# CarrierPeripherals.net
KiCad netlist of a schematic drawn in Altium Designer
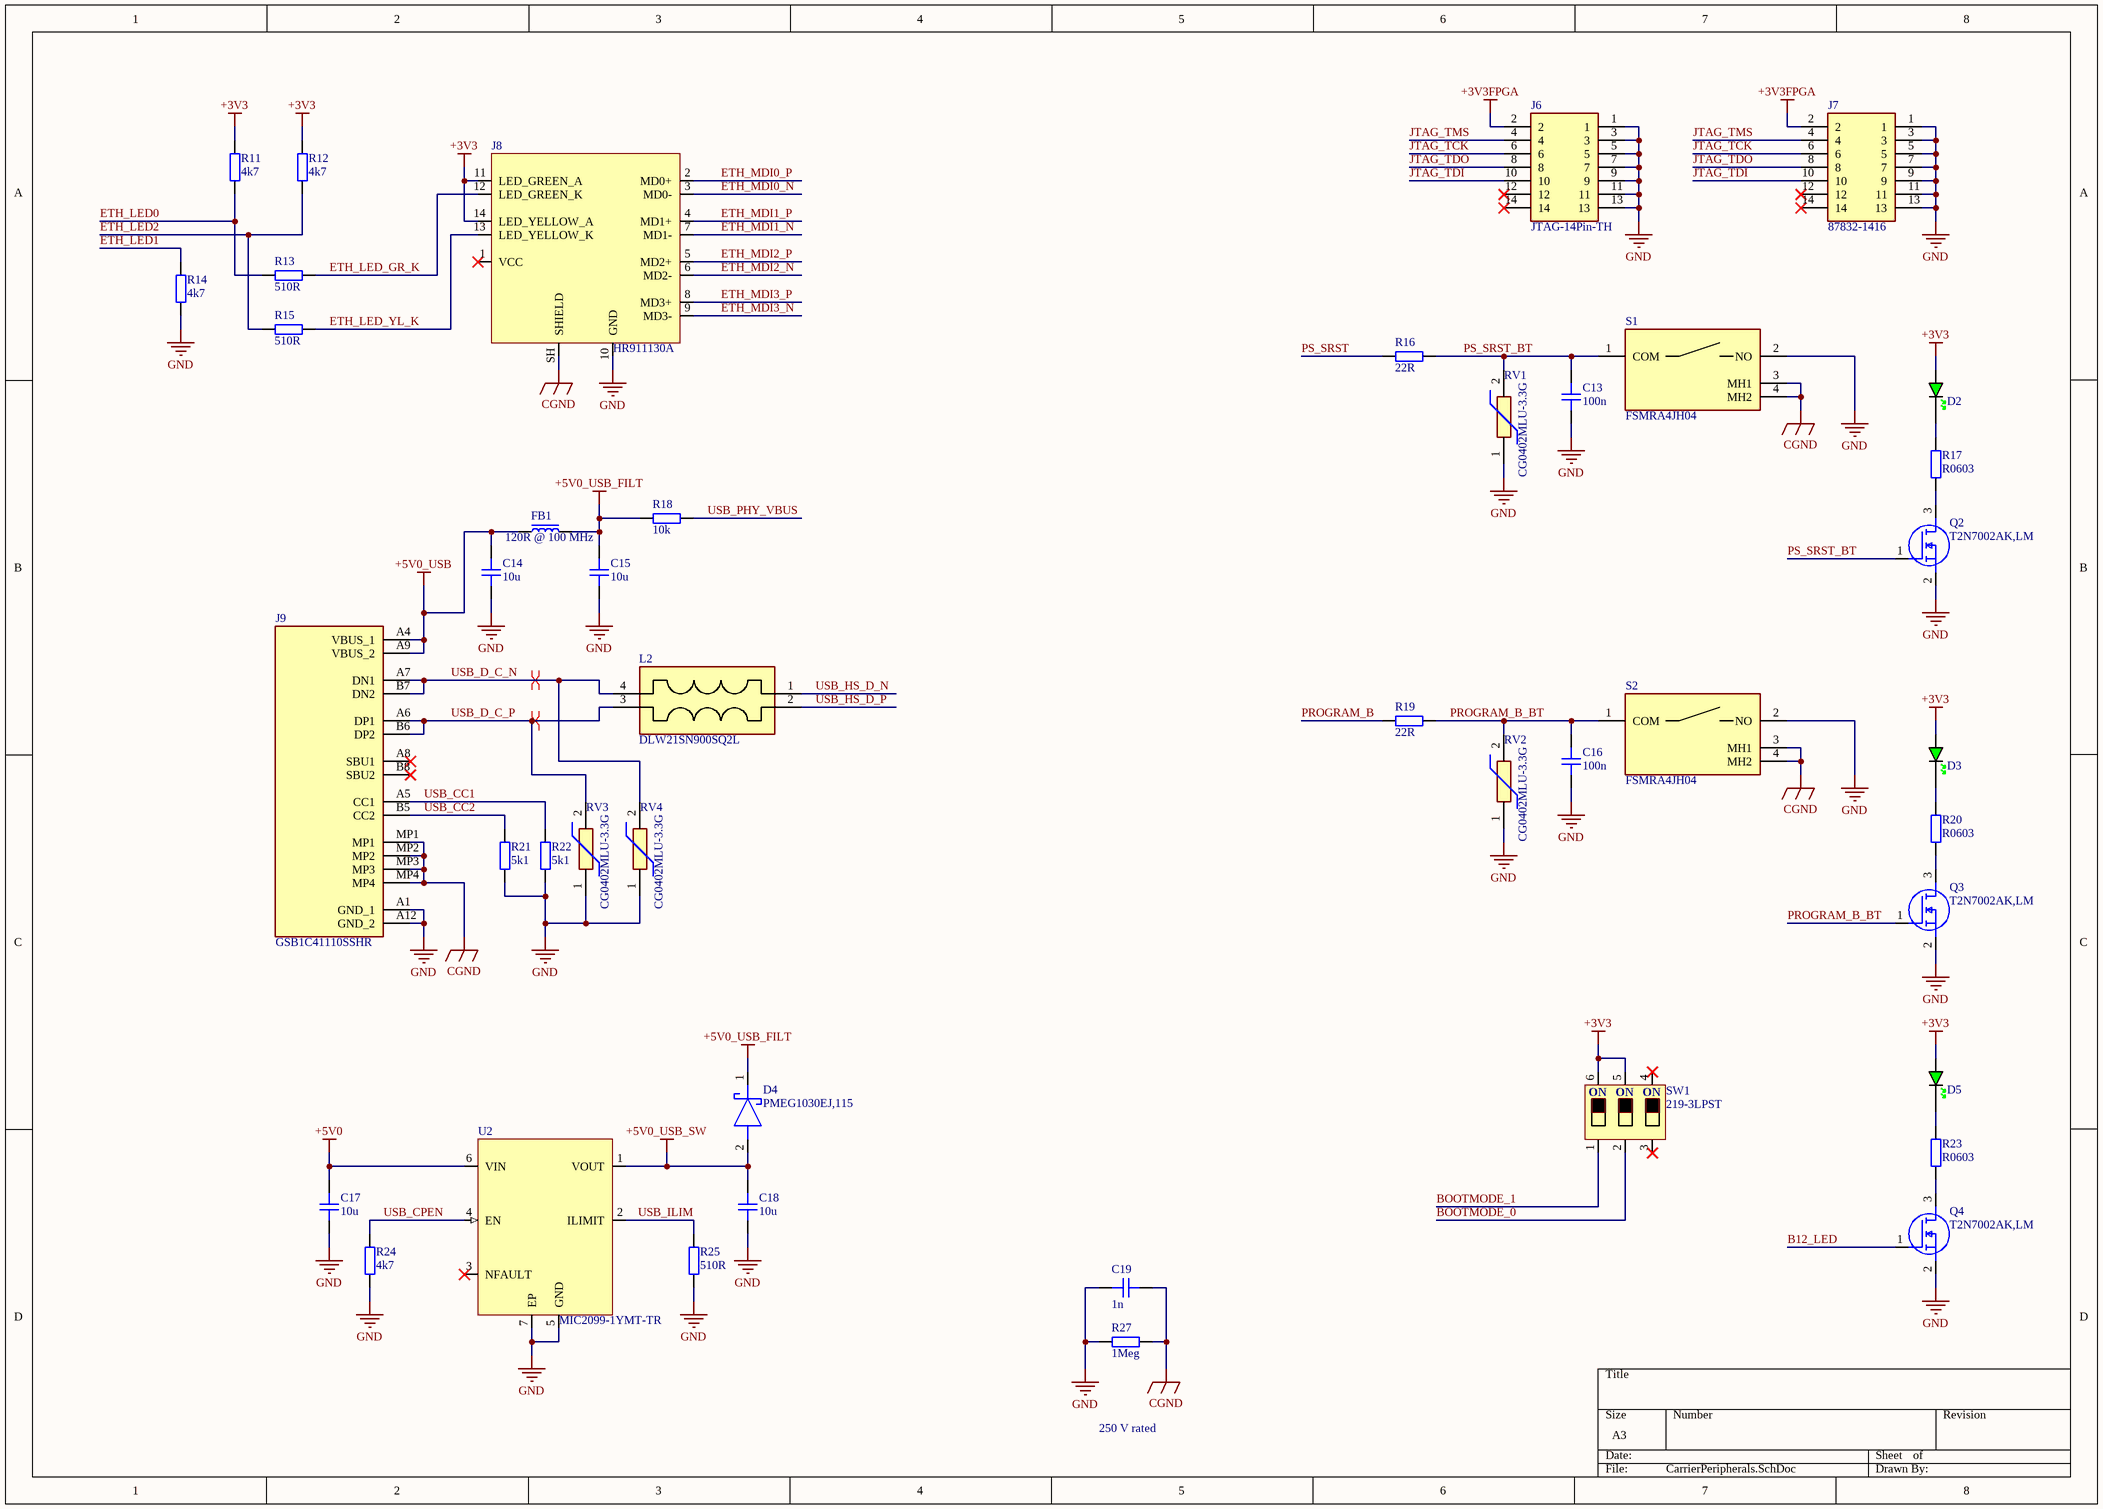
[diagram p0: CarrierPeripherals.SchDoc]

(export (version "E")
  (design (tool "Eeschema 10.0.6"))
  (components
    (comp (ref "C13")
      (value "100n")
      (footprint "CAP_0402")
      (description "Capacitor SMD 0402")
      (libsource (lib "Schematic-Lib-PhilsLab") (part "CAP_0402"))
    )
    (comp (ref "C14")
      (value "10u")
      (footprint "CAP_0603")
      (description "Capacitor SMD 0603")
      (libsource (lib "Schematic-Lib-PhilsLab") (part "CAP_0603"))
    )
    (comp (ref "C15")
      (value "10u")
      (footprint "CAP_0603")
      (description "Capacitor SMD 0603")
      (libsource (lib "Schematic-Lib-PhilsLab") (part "CAP_0603"))
    )
    (comp (ref "C16")
      (value "100n")
      (footprint "CAP_0402")
      (description "Capacitor SMD 0402")
      (libsource (lib "Schematic-Lib-PhilsLab") (part "CAP_0402"))
    )
    (comp (ref "C17")
      (value "10u")
      (footprint "CAP_0603")
      (description "Capacitor SMD 0603")
      (libsource (lib "Schematic-Lib-PhilsLab") (part "CAP_0603"))
    )
    (comp (ref "C18")
      (value "10u")
      (footprint "CAP_0603")
      (description "Capacitor SMD 0603")
      (libsource (lib "Schematic-Lib-PhilsLab") (part "CAP_0603"))
    )
    (comp (ref "C19")
      (value "1n")
      (footprint "CAP_1206")
      (description "Capacitor SMD 1206")
      (libsource (lib "Schematic-Lib-PhilsLab") (part "CAP_1206"))
    )
    (comp (ref "D2")
      (value "GREEN")
      (footprint "LED_0603_GREEN")
      (description "LED 0603 GREEN SMD")
      (libsource (lib "Schematic-Lib-PhilsLab") (part "LED_0603_GREEN"))
    )
    (comp (ref "D3")
      (value "GREEN")
      (footprint "LED_0603_GREEN")
      (description "LED 0603 GREEN SMD")
      (libsource (lib "Schematic-Lib-PhilsLab") (part "LED_0603_GREEN"))
    )
    (comp (ref "D4")
      (value "PMEG1030EJ,115")
      (footprint "CarrierBoardPCBLib:PMEG1030EJ115")
      (description "Schottky Diode")
      (fields (field (name "MOUSER PART NUMBER") "771-PMEG1030EJ-T/R"))
      (libsource (lib "CarrierBoardSCHLib") (part "PMEG1030EJ,115"))
    )
    (comp (ref "D5")
      (value "GREEN")
      (footprint "LED_0603_GREEN")
      (description "LED 0603 GREEN SMD")
      (libsource (lib "Schematic-Lib-PhilsLab") (part "LED_0603_GREEN"))
    )
    (comp (ref "FB1")
      (value "120R @ 100 MHz")
      (footprint "FB_0603")
      (description "Ferrite Bead SMD 0603")
      (libsource (lib "Schematic-Lib-PhilsLab") (part "FB_0603"))
    )
    (comp (ref "J6")
      (value "JTAG-14Pin-TH")
      (footprint "XC7Z030PCBLib:14Pin-TH")
      (description "Connector")
      (fields
        (field (name "MANUFACTURER_PART_NUMBER") "87832-1416")
        (field (name "MOUSER PART NUMBER") "538-87832-1416")
      )
      (libsource (lib "XC7Z030SCHLib") (part "JTAG-14Pin-TH"))
    )
    (comp (ref "J7")
      (value "87832-1416")
      (footprint "XC7Z030PCBLib:878321416")
      (description "Connector")
      (fields (field (name "MOUSER PART NUMBER") "538-87832-1416"))
      (libsource (lib "XC7Z030SCHLib") (part "87832-1416"))
    )
    (comp (ref "J8")
      (value "HR911130A")
      (footprint "HR911130A")
      (description "100/1000Base-T Magnetics Single-Port RJ45 Connector with Integrated Magnetics and LEDs")
      (fields (field (name "MANUFACTURER") "Hanrun"))
      (libsource (lib "Schematic-Lib-PhilsLab") (part "HR911130A"))
    )
    (comp (ref "J9")
      (value "GSB1C41110SSHR")
      (footprint "XC7Z030PCBLib:GSB1C41110SSHR")
      (description "Connector")
      (libsource (lib "XC7Z030SCHLib") (part "GSB1C41110SSHR"))
    )
    (comp (ref "L2")
      (value "DLW21SN900SQ2L")
      (footprint "CarrierBoardPCBLib:DLW21SN121HQ2L")
      (description "Inductor")
      (fields (field (name "MOUSER PART NUMBER") "81-DLW21SN900SQ2L"))
      (libsource (lib "CarrierBoardSCHLib") (part "DLW21SN900SQ2L"))
    )
    (comp (ref "Q2")
      (value "T2N7002AK,LM")
      (footprint "Footprint-Lib-PhilsLab:TBAT54CLM")
      (description "MOSFET (N-Channel)")
      (fields (field (name "MOUSER PART NUMBER") "757-T2N7002AKLM"))
      (libsource (lib "Schematic-Lib-PhilsLab") (part "T2N7002AK,LM"))
    )
    (comp (ref "Q3")
      (value "T2N7002AK,LM")
      (footprint "Footprint-Lib-PhilsLab:TBAT54CLM")
      (description "MOSFET (N-Channel)")
      (fields (field (name "MOUSER PART NUMBER") "757-T2N7002AKLM"))
      (libsource (lib "Schematic-Lib-PhilsLab") (part "T2N7002AK,LM"))
    )
    (comp (ref "Q4")
      (value "T2N7002AK,LM")
      (footprint "Footprint-Lib-PhilsLab:TBAT54CLM")
      (description "MOSFET (N-Channel)")
      (fields (field (name "MOUSER PART NUMBER") "757-T2N7002AKLM"))
      (libsource (lib "Schematic-Lib-PhilsLab") (part "T2N7002AK,LM"))
    )
    (comp (ref "R11")
      (value "4k7")
      (footprint "RES_0402")
      (description "Resistor SMD 0402")
      (libsource (lib "Schematic-Lib-PhilsLab") (part "RES_0402"))
    )
    (comp (ref "R12")
      (value "4k7")
      (footprint "RES_0402")
      (description "Resistor SMD 0402")
      (libsource (lib "Schematic-Lib-PhilsLab") (part "RES_0402"))
    )
    (comp (ref "R13")
      (value "510R")
      (footprint "RES_0603")
      (description "Resistor SMD 0603")
      (libsource (lib "Schematic-Lib-PhilsLab") (part "RES_0603"))
    )
    (comp (ref "R14")
      (value "4k7")
      (footprint "RES_0402")
      (description "Resistor SMD 0402")
      (libsource (lib "Schematic-Lib-PhilsLab") (part "RES_0402"))
    )
    (comp (ref "R15")
      (value "510R")
      (footprint "RES_0603")
      (description "Resistor SMD 0603")
      (libsource (lib "Schematic-Lib-PhilsLab") (part "RES_0603"))
    )
    (comp (ref "R16")
      (value "22R")
      (footprint "RES_0402")
      (description "Resistor SMD 0402")
      (libsource (lib "Schematic-Lib-PhilsLab") (part "RES_0402"))
    )
    (comp (ref "R17")
      (value "R0603")
      (footprint "RES_0603")
      (description "Resistor SMD 0603")
      (libsource (lib "Schematic-Lib-PhilsLab") (part "RES_0603"))
    )
    (comp (ref "R18")
      (value "10k")
      (footprint "RES_0402")
      (description "Resistor SMD 0402")
      (libsource (lib "Schematic-Lib-PhilsLab") (part "RES_0402"))
    )
    (comp (ref "R19")
      (value "22R")
      (footprint "RES_0402")
      (description "Resistor SMD 0402")
      (libsource (lib "Schematic-Lib-PhilsLab") (part "RES_0402"))
    )
    (comp (ref "R20")
      (value "R0603")
      (footprint "RES_0603")
      (description "Resistor SMD 0603")
      (libsource (lib "Schematic-Lib-PhilsLab") (part "RES_0603"))
    )
    (comp (ref "R21")
      (value "5k1")
      (footprint "RES_0402")
      (description "Resistor SMD 0402")
      (libsource (lib "Schematic-Lib-PhilsLab") (part "RES_0402"))
    )
    (comp (ref "R22")
      (value "5k1")
      (footprint "RES_0402")
      (description "Resistor SMD 0402")
      (libsource (lib "Schematic-Lib-PhilsLab") (part "RES_0402"))
    )
    (comp (ref "R23")
      (value "R0603")
      (footprint "RES_0603")
      (description "Resistor SMD 0603")
      (libsource (lib "Schematic-Lib-PhilsLab") (part "RES_0603"))
    )
    (comp (ref "R24")
      (value "4k7")
      (footprint "RES_0402")
      (description "Resistor SMD 0402")
      (libsource (lib "Schematic-Lib-PhilsLab") (part "RES_0402"))
    )
    (comp (ref "R25")
      (value "510R")
      (footprint "RES_0603")
      (description "Resistor SMD 0603")
      (libsource (lib "Schematic-Lib-PhilsLab") (part "RES_0603"))
    )
    (comp (ref "R27")
      (value "1Meg")
      (footprint "RES_1206")
      (description "Resistor SMD 1206")
      (libsource (lib "Schematic-Lib-PhilsLab") (part "RES_1206"))
    )
    (comp (ref "RV1")
      (value "CG0402MLU-3.3G")
      (footprint "CarrierBoardPCBLib:VARC1005X41N")
      (description "ESD Diode")
      (fields (field (name "MOUSER PART NUMBER") "652-CG0402MLU-3.3G"))
      (libsource (lib "CarrierBoardSCHLib") (part "CG0402MLU-3.3G"))
    )
    (comp (ref "RV2")
      (value "CG0402MLU-3.3G")
      (footprint "CarrierBoardPCBLib:VARC1005X41N")
      (description "ESD Diode")
      (fields (field (name "MOUSER PART NUMBER") "652-CG0402MLU-3.3G"))
      (libsource (lib "CarrierBoardSCHLib") (part "CG0402MLU-3.3G"))
    )
    (comp (ref "RV3")
      (value "CG0402MLU-3.3G")
      (footprint "CarrierBoardPCBLib:VARC1005X41N")
      (description "ESD Diode")
      (fields (field (name "MOUSER PART NUMBER") "652-CG0402MLU-3.3G"))
      (libsource (lib "CarrierBoardSCHLib") (part "CG0402MLU-3.3G"))
    )
    (comp (ref "RV4")
      (value "CG0402MLU-3.3G")
      (footprint "CarrierBoardPCBLib:VARC1005X41N")
      (description "ESD Diode")
      (fields (field (name "MOUSER PART NUMBER") "652-CG0402MLU-3.3G"))
      (libsource (lib "CarrierBoardSCHLib") (part "CG0402MLU-3.3G"))
    )
    (comp (ref "S1")
      (value "FSMRA4JH04")
      (footprint "CarrierBoardPCBLib:FSMRA4JH04")
      (description "Switch")
      (fields (field (name "MOUSER PART NUMBER") "506-FSMRA4JH04"))
      (libsource (lib "CarrierBoardSCHLib") (part "FSMRA4JH04"))
    )
    (comp (ref "S2")
      (value "FSMRA4JH04")
      (footprint "CarrierBoardPCBLib:FSMRA4JH04")
      (description "Switch")
      (fields (field (name "MOUSER PART NUMBER") "506-FSMRA4JH04"))
      (libsource (lib "CarrierBoardSCHLib") (part "FSMRA4JH04"))
    )
    (comp (ref "SW1")
      (value "219-3LPST")
      (footprint "219-3LPST")
      (description "DIP Switches SPST 3x")
      (fields (field (name "MANUFACTURER") "CTS"))
      (libsource (lib "Schematic-Lib-PhilsLab") (part "219-3LPST"))
    )
    (comp (ref "U2")
      (value "MIC2099-1YMT-TR")
      (footprint "TMLF-6-1_6X1_6")
      (description "Power Distribution Switch Resistor programmable current limit\r\n– 0.1A to 1.1A 2.5V-5.5V")
      (fields (field (name "MANUFACTURER") "Microchip"))
      (libsource (lib "Schematic-Lib-PhilsLab") (part "MIC2099-1YMT-TR"))
    )
  )
  (nets
    (net (code "1") (name "+3V3") (class "Default")
      (node (ref "D2") (pin "A") (pinfunction "A_A") (pintype "passive"))
      (node (ref "D3") (pin "A") (pinfunction "A_A") (pintype "passive"))
      (node (ref "D5") (pin "A") (pinfunction "A_A") (pintype "passive"))
      (node (ref "J8") (pin "11") (pinfunction "LED_GREEN_A_11") (pintype "passive"))
      (node (ref "J8") (pin "14") (pinfunction "LED_YELLOW_A_14") (pintype "passive"))
      (node (ref "R11") (pin "2") (pinfunction "2_2") (pintype "passive"))
      (node (ref "R12") (pin "2") (pinfunction "2_2") (pintype "passive"))
      (node (ref "SW1") (pin "5") (pinfunction "5_5") (pintype "passive"))
      (node (ref "SW1") (pin "6") (pinfunction "6_6") (pintype "passive"))
    )
    (net (code "2") (name "+3V3FPGA") (class "Default")
      (node (ref "J6") (pin "2") (pinfunction "2_2") (pintype "passive"))
      (node (ref "J7") (pin "2") (pinfunction "2_2") (pintype "passive"))
    )
    (net (code "3") (name "+5V0") (class "Default")
      (node (ref "C17") (pin "2") (pinfunction "2_2") (pintype "passive"))
      (node (ref "U2") (pin "6") (pinfunction "VIN_6") (pintype "power_in"))
    )
    (net (code "4") (name "+5V0_USB") (class "Default")
      (node (ref "C14") (pin "2") (pinfunction "2_2") (pintype "passive"))
      (node (ref "FB1") (pin "1") (pinfunction "1_1") (pintype "passive"))
      (node (ref "J9") (pin "A4") (pinfunction "VBUS_1_A4") (pintype "passive"))
      (node (ref "J9") (pin "A9") (pinfunction "VBUS_2_A9") (pintype "passive"))
    )
    (net (code "5") (name "+5V0_USB_FILT") (class "Default")
      (node (ref "C15") (pin "2") (pinfunction "2_2") (pintype "passive"))
      (node (ref "D4") (pin "1") (pinfunction "K_1") (pintype "passive"))
      (node (ref "FB1") (pin "2") (pinfunction "2_2") (pintype "passive"))
      (node (ref "R18") (pin "1") (pinfunction "1_1") (pintype "passive"))
    )
    (net (code "6") (name "+5V0_USB_SW") (class "Default")
      (node (ref "C18") (pin "2") (pinfunction "2_2") (pintype "passive"))
      (node (ref "D4") (pin "2") (pinfunction "A_2") (pintype "passive"))
      (node (ref "U2") (pin "1") (pinfunction "VOUT_1") (pintype "power_in"))
    )
    (net (code "7") (name "/B12_LED") (class "Default")
      (node (ref "Q4") (pin "1") (pinfunction "G_1") (pintype "passive"))
    )
    (net (code "8") (name "/BOOTMODE_0") (class "Default")
      (node (ref "SW1") (pin "2") (pinfunction "2_2") (pintype "passive"))
    )
    (net (code "9") (name "/BOOTMODE_1") (class "Default")
      (node (ref "SW1") (pin "1") (pinfunction "1_1") (pintype "passive"))
    )
    (net (code "10") (name "/ETH_LED0") (class "Default")
      (node (ref "R11") (pin "1") (pinfunction "1_1") (pintype "passive"))
      (node (ref "R13") (pin "1") (pinfunction "1_1") (pintype "passive"))
    )
    (net (code "11") (name "/ETH_LED1") (class "Default")
      (node (ref "R14") (pin "2") (pinfunction "2_2") (pintype "passive"))
    )
    (net (code "12") (name "/ETH_LED2") (class "Default")
      (node (ref "R12") (pin "1") (pinfunction "1_1") (pintype "passive"))
      (node (ref "R15") (pin "2") (pinfunction "2_2") (pintype "passive"))
    )
    (net (code "13") (name "/ETH_LED_GR_K") (class "Default")
      (node (ref "J8") (pin "12") (pinfunction "LED_GREEN_K_12") (pintype "passive"))
      (node (ref "R13") (pin "2") (pinfunction "2_2") (pintype "passive"))
    )
    (net (code "14") (name "/ETH_LED_YL_K") (class "Default")
      (node (ref "J8") (pin "13") (pinfunction "LED_YELLOW_K_13") (pintype "passive"))
      (node (ref "R15") (pin "1") (pinfunction "1_1") (pintype "passive"))
    )
    (net (code "15") (name "/ETH_MDI0_N") (class "Default")
      (node (ref "J8") (pin "3") (pinfunction "MD0-_3") (pintype "passive"))
    )
    (net (code "16") (name "/ETH_MDI0_P") (class "Default")
      (node (ref "J8") (pin "2") (pinfunction "MD0+_2") (pintype "passive"))
    )
    (net (code "17") (name "/ETH_MDI1_N") (class "Default")
      (node (ref "J8") (pin "7") (pinfunction "MD1-_7") (pintype "passive"))
    )
    (net (code "18") (name "/ETH_MDI1_P") (class "Default")
      (node (ref "J8") (pin "4") (pinfunction "MD1+_4") (pintype "passive"))
    )
    (net (code "19") (name "/ETH_MDI2_N") (class "Default")
      (node (ref "J8") (pin "6") (pinfunction "MD2-_6") (pintype "passive"))
    )
    (net (code "20") (name "/ETH_MDI2_P") (class "Default")
      (node (ref "J8") (pin "5") (pinfunction "MD2+_5") (pintype "passive"))
    )
    (net (code "21") (name "/ETH_MDI3_N") (class "Default")
      (node (ref "J8") (pin "9") (pinfunction "MD3-_9") (pintype "passive"))
    )
    (net (code "22") (name "/ETH_MDI3_P") (class "Default")
      (node (ref "J8") (pin "8") (pinfunction "MD3+_8") (pintype "passive"))
    )
    (net (code "23") (name "/JTAG_TCK") (class "Default")
      (node (ref "J6") (pin "6") (pinfunction "6_6") (pintype "passive"))
      (node (ref "J7") (pin "6") (pinfunction "6_6") (pintype "passive"))
    )
    (net (code "24") (name "/JTAG_TDI") (class "Default")
      (node (ref "J6") (pin "10") (pinfunction "10_10") (pintype "passive"))
      (node (ref "J7") (pin "10") (pinfunction "10_10") (pintype "passive"))
    )
    (net (code "25") (name "/JTAG_TDO") (class "Default")
      (node (ref "J6") (pin "8") (pinfunction "8_8") (pintype "passive"))
      (node (ref "J7") (pin "8") (pinfunction "8_8") (pintype "passive"))
    )
    (net (code "26") (name "/JTAG_TMS") (class "Default")
      (node (ref "J6") (pin "4") (pinfunction "4_4") (pintype "passive"))
      (node (ref "J7") (pin "4") (pinfunction "4_4") (pintype "passive"))
    )
    (net (code "27") (name "/PROGRAM_B") (class "Default")
      (node (ref "R19") (pin "2") (pinfunction "2_2") (pintype "passive"))
    )
    (net (code "28") (name "/PROGRAM_B_BT") (class "Default")
      (node (ref "C16") (pin "2") (pinfunction "2_2") (pintype "passive"))
      (node (ref "Q3") (pin "1") (pinfunction "G_1") (pintype "passive"))
      (node (ref "R19") (pin "1") (pinfunction "1_1") (pintype "passive"))
      (node (ref "RV2") (pin "2") (pinfunction "2_2") (pintype "passive"))
      (node (ref "S2") (pin "1") (pinfunction "COM_1") (pintype "passive"))
    )
    (net (code "29") (name "/PS_SRST") (class "Default")
      (node (ref "R16") (pin "2") (pinfunction "2_2") (pintype "passive"))
    )
    (net (code "30") (name "/PS_SRST_BT") (class "Default")
      (node (ref "C13") (pin "2") (pinfunction "2_2") (pintype "passive"))
      (node (ref "Q2") (pin "1") (pinfunction "G_1") (pintype "passive"))
      (node (ref "R16") (pin "1") (pinfunction "1_1") (pintype "passive"))
      (node (ref "RV1") (pin "2") (pinfunction "2_2") (pintype "passive"))
      (node (ref "S1") (pin "1") (pinfunction "COM_1") (pintype "passive"))
    )
    (net (code "31") (name "/USB_CC1") (class "Default")
      (node (ref "J9") (pin "A5") (pinfunction "CC1_A5") (pintype "passive"))
      (node (ref "R22") (pin "2") (pinfunction "2_2") (pintype "passive"))
    )
    (net (code "32") (name "/USB_CC2") (class "Default")
      (node (ref "J9") (pin "B5") (pinfunction "CC2_B5") (pintype "passive"))
      (node (ref "R21") (pin "2") (pinfunction "2_2") (pintype "passive"))
    )
    (net (code "33") (name "/USB_CPEN") (class "Default")
      (node (ref "R24") (pin "2") (pinfunction "2_2") (pintype "passive"))
      (node (ref "U2") (pin "4") (pinfunction "EN_4") (pintype "input"))
    )
    (net (code "34") (name "/USB_D_C_N") (class "Default")
      (node (ref "J9") (pin "A7") (pinfunction "DN1_A7") (pintype "passive"))
      (node (ref "J9") (pin "B7") (pinfunction "DN2_B7") (pintype "passive"))
      (node (ref "L2") (pin "4") (pintype "passive"))
      (node (ref "RV4") (pin "2") (pinfunction "2_2") (pintype "passive"))
    )
    (net (code "35") (name "/USB_D_C_P") (class "Default")
      (node (ref "J9") (pin "A6") (pinfunction "DP1_A6") (pintype "passive"))
      (node (ref "J9") (pin "B6") (pinfunction "DP2_B6") (pintype "passive"))
      (node (ref "L2") (pin "3") (pintype "passive"))
      (node (ref "RV3") (pin "2") (pinfunction "2_2") (pintype "passive"))
    )
    (net (code "36") (name "/USB_HS_D_N") (class "Default") (node (ref "L2") (pin "1") (pintype "passive")))
    (net (code "37") (name "/USB_HS_D_P") (class "Default") (node (ref "L2") (pin "2") (pintype "passive")))
    (net (code "38") (name "/USB_ILIM") (class "Default")
      (node (ref "R25") (pin "2") (pinfunction "2_2") (pintype "passive"))
      (node (ref "U2") (pin "2") (pinfunction "ILIMIT_2") (pintype "passive"))
    )
    (net (code "39") (name "/USB_PHY_VBUS") (class "Default")
      (node (ref "R18") (pin "2") (pinfunction "2_2") (pintype "passive"))
    )
    (net (code "40") (name "CGND") (class "Default")
      (node (ref "C19") (pin "2") (pinfunction "2_2") (pintype "passive"))
      (node (ref "J8") (pin "SH") (pinfunction "SHIELD_SH") (pintype "passive"))
      (node (ref "J9") (pin "MP1") (pinfunction "MP1_MP1") (pintype "passive"))
      (node (ref "J9") (pin "MP2") (pinfunction "MP2_MP2") (pintype "passive"))
      (node (ref "J9") (pin "MP3") (pinfunction "MP3_MP3") (pintype "passive"))
      (node (ref "J9") (pin "MP4") (pinfunction "MP4_MP4") (pintype "passive"))
      (node (ref "R27") (pin "2") (pinfunction "2_2") (pintype "passive"))
      (node (ref "S1") (pin "3") (pinfunction "MH1_3") (pintype "passive"))
      (node (ref "S1") (pin "4") (pinfunction "MH2_4") (pintype "passive"))
      (node (ref "S2") (pin "3") (pinfunction "MH1_3") (pintype "passive"))
      (node (ref "S2") (pin "4") (pinfunction "MH2_4") (pintype "passive"))
    )
    (net (code "41") (name "GND") (class "Default")
      (node (ref "C13") (pin "1") (pinfunction "1_1") (pintype "passive"))
      (node (ref "C14") (pin "1") (pinfunction "1_1") (pintype "passive"))
      (node (ref "C15") (pin "1") (pinfunction "1_1") (pintype "passive"))
      (node (ref "C16") (pin "1") (pinfunction "1_1") (pintype "passive"))
      (node (ref "C17") (pin "1") (pinfunction "1_1") (pintype "passive"))
      (node (ref "C18") (pin "1") (pinfunction "1_1") (pintype "passive"))
      (node (ref "C19") (pin "1") (pinfunction "1_1") (pintype "passive"))
      (node (ref "J6") (pin "1") (pinfunction "1_1") (pintype "passive"))
      (node (ref "J6") (pin "11") (pinfunction "11_11") (pintype "passive"))
      (node (ref "J6") (pin "13") (pinfunction "13_13") (pintype "passive"))
      (node (ref "J6") (pin "3") (pinfunction "3_3") (pintype "passive"))
      (node (ref "J6") (pin "5") (pinfunction "5_5") (pintype "passive"))
      (node (ref "J6") (pin "7") (pinfunction "7_7") (pintype "passive"))
      (node (ref "J6") (pin "9") (pinfunction "9_9") (pintype "passive"))
      (node (ref "J7") (pin "1") (pinfunction "1_1") (pintype "passive"))
      (node (ref "J7") (pin "11") (pinfunction "11_11") (pintype "passive"))
      (node (ref "J7") (pin "13") (pinfunction "13_13") (pintype "passive"))
      (node (ref "J7") (pin "3") (pinfunction "3_3") (pintype "passive"))
      (node (ref "J7") (pin "5") (pinfunction "5_5") (pintype "passive"))
      (node (ref "J7") (pin "7") (pinfunction "7_7") (pintype "passive"))
      (node (ref "J7") (pin "9") (pinfunction "9_9") (pintype "passive"))
      (node (ref "J8") (pin "10") (pinfunction "GND_10") (pintype "passive"))
      (node (ref "J9") (pin "A1") (pinfunction "GND_1_A1") (pintype "passive"))
      (node (ref "J9") (pin "A12") (pinfunction "GND_2_A12") (pintype "passive"))
      (node (ref "Q2") (pin "2") (pinfunction "S_2") (pintype "passive"))
      (node (ref "Q3") (pin "2") (pinfunction "S_2") (pintype "passive"))
      (node (ref "Q4") (pin "2") (pinfunction "S_2") (pintype "passive"))
      (node (ref "R14") (pin "1") (pinfunction "1_1") (pintype "passive"))
      (node (ref "R21") (pin "1") (pinfunction "1_1") (pintype "passive"))
      (node (ref "R22") (pin "1") (pinfunction "1_1") (pintype "passive"))
      (node (ref "R24") (pin "1") (pinfunction "1_1") (pintype "passive"))
      (node (ref "R25") (pin "1") (pinfunction "1_1") (pintype "passive"))
      (node (ref "R27") (pin "1") (pinfunction "1_1") (pintype "passive"))
      (node (ref "RV1") (pin "1") (pinfunction "1_1") (pintype "passive"))
      (node (ref "RV2") (pin "1") (pinfunction "1_1") (pintype "passive"))
      (node (ref "RV3") (pin "1") (pinfunction "1_1") (pintype "passive"))
      (node (ref "RV4") (pin "1") (pinfunction "1_1") (pintype "passive"))
      (node (ref "S1") (pin "2") (pinfunction "NO_2") (pintype "passive"))
      (node (ref "S2") (pin "2") (pinfunction "NO_2") (pintype "passive"))
      (node (ref "U2") (pin "5") (pinfunction "GND_5") (pintype "power_in"))
      (node (ref "U2") (pin "7") (pinfunction "EP_7") (pintype "power_in"))
    )
    (net (code "42") (name "Net-(D2-PadK)") (class "Default")
      (node (ref "D2") (pin "K") (pinfunction "K_K") (pintype "passive"))
      (node (ref "R17") (pin "2") (pinfunction "2_2") (pintype "passive"))
    )
    (net (code "43") (name "Net-(D3-PadK)") (class "Default")
      (node (ref "D3") (pin "K") (pinfunction "K_K") (pintype "passive"))
      (node (ref "R20") (pin "2") (pinfunction "2_2") (pintype "passive"))
    )
    (net (code "44") (name "Net-(D5-PadK)") (class "Default")
      (node (ref "D5") (pin "K") (pinfunction "K_K") (pintype "passive"))
      (node (ref "R23") (pin "2") (pinfunction "2_2") (pintype "passive"))
    )
    (net (code "45") (name "Net-(Q2-D)") (class "Default")
      (node (ref "Q2") (pin "3") (pinfunction "D_3") (pintype "passive"))
      (node (ref "R17") (pin "1") (pinfunction "1_1") (pintype "passive"))
    )
    (net (code "46") (name "Net-(Q3-D)") (class "Default")
      (node (ref "Q3") (pin "3") (pinfunction "D_3") (pintype "passive"))
      (node (ref "R20") (pin "1") (pinfunction "1_1") (pintype "passive"))
    )
    (net (code "47") (name "Net-(Q4-D)") (class "Default")
      (node (ref "Q4") (pin "3") (pinfunction "D_3") (pintype "passive"))
      (node (ref "R23") (pin "1") (pinfunction "1_1") (pintype "passive"))
    )
    (net (code "48") (name "unconnected-(J6-Pad12)") (class "Default")
      (node (ref "J6") (pin "12") (pinfunction "12_12") (pintype "passive+no_connect"))
    )
    (net (code "49") (name "unconnected-(J6-Pad14)") (class "Default")
      (node (ref "J6") (pin "14") (pinfunction "14_14") (pintype "passive+no_connect"))
    )
    (net (code "50") (name "unconnected-(J7-Pad12)") (class "Default")
      (node (ref "J7") (pin "12") (pinfunction "12_12") (pintype "passive+no_connect"))
    )
    (net (code "51") (name "unconnected-(J7-Pad14)") (class "Default")
      (node (ref "J7") (pin "14") (pinfunction "14_14") (pintype "passive+no_connect"))
    )
    (net (code "52") (name "unconnected-(J8-VCC-Pad1)") (class "Default")
      (node (ref "J8") (pin "1") (pinfunction "VCC_1") (pintype "passive+no_connect"))
    )
    (net (code "53") (name "unconnected-(J9-SBU1-PadA8)") (class "Default")
      (node (ref "J9") (pin "A8") (pinfunction "SBU1_A8") (pintype "passive+no_connect"))
    )
    (net (code "54") (name "unconnected-(J9-SBU2-PadB8)") (class "Default")
      (node (ref "J9") (pin "B8") (pinfunction "SBU2_B8") (pintype "passive+no_connect"))
    )
    (net (code "55") (name "unconnected-(SW1-Pad3)") (class "Default")
      (node (ref "SW1") (pin "3") (pinfunction "3_3") (pintype "passive+no_connect"))
    )
    (net (code "56") (name "unconnected-(SW1-Pad4)") (class "Default")
      (node (ref "SW1") (pin "4") (pinfunction "4_4") (pintype "passive+no_connect"))
    )
    (net (code "57") (name "unconnected-(U2-NFAULT-Pad3)") (class "Default")
      (node (ref "U2") (pin "3") (pinfunction "NFAULT_3") (pintype "open_collector+no_connect"))
    )
  )
)
